# MCU_144_POWER_Clone.net
KiCad netlist of a schematic drawn in Altium Designer
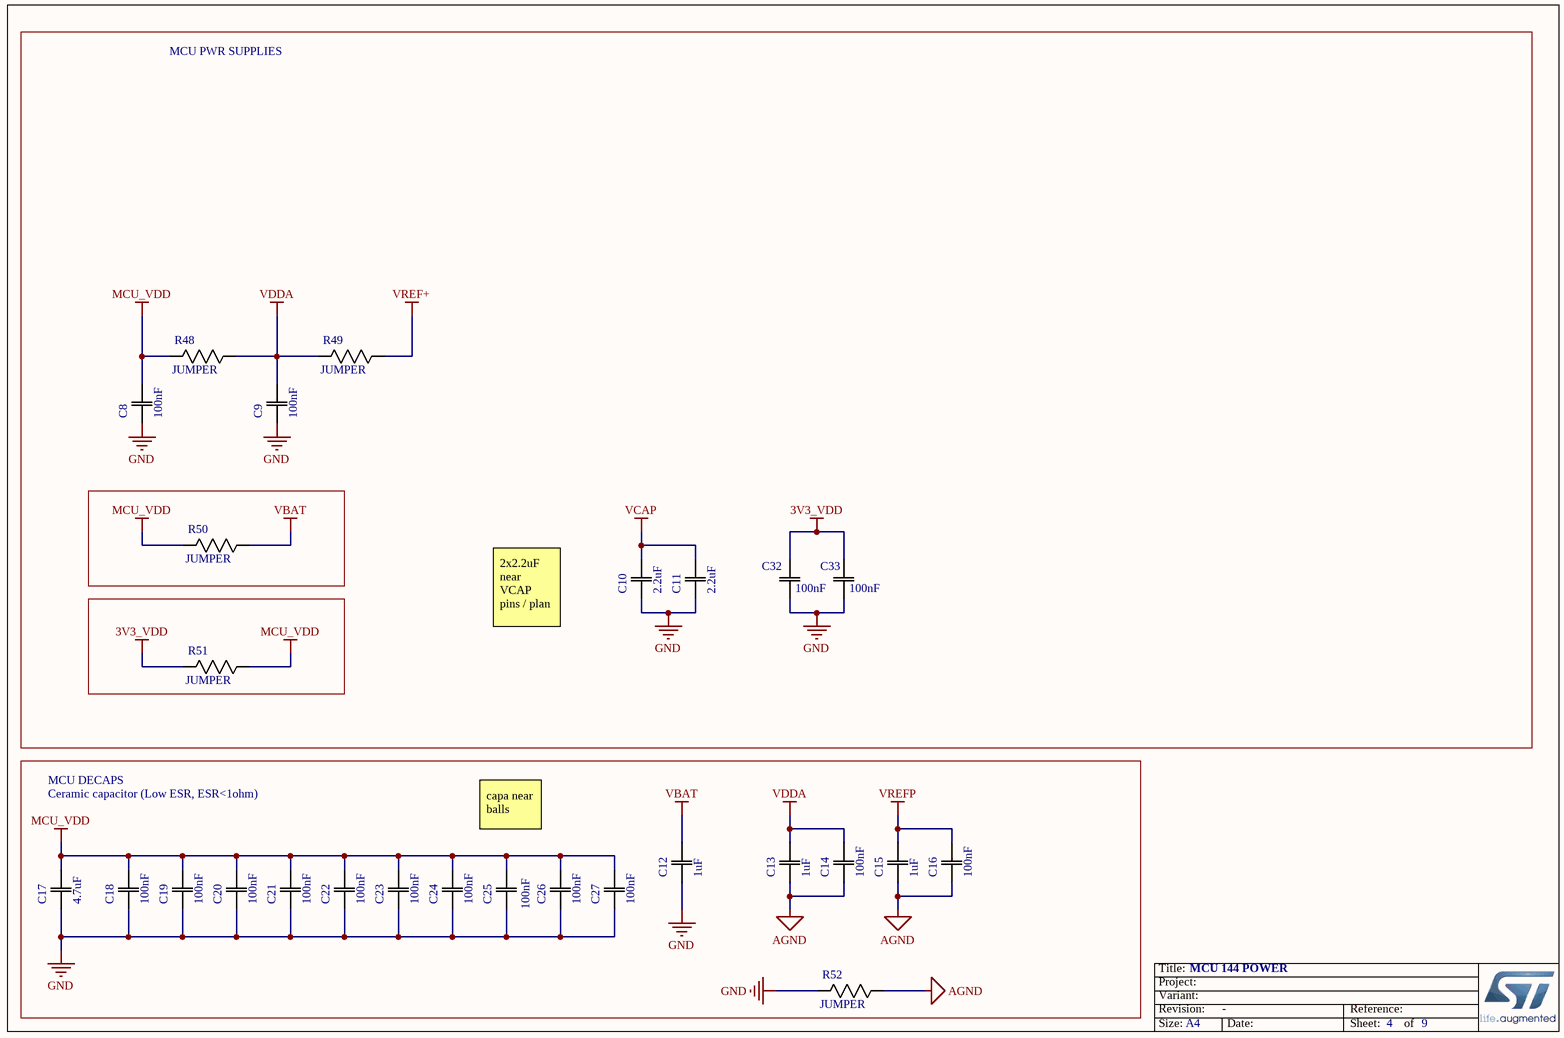
[diagram p0: MCU_144_POWER_Clone.SchDoc]

(export (version "E")
  (design (tool "Eeschema 10.0.6"))
  (components
    (comp (ref "C8")
      (value "100nF")
      (footprint "0805")
      (description "CAP CER 0.1UF 50V X7R 0805")
      (fields (field (name "MP") "CC0805KRX7R9BB104") (field (name "MF") "Yageo"))
      (libsource (lib "AltiumLibraries") (part "CAP 100nF 0805"))
    )
    (comp (ref "C9")
      (value "100nF")
      (footprint "0805")
      (description "CAP CER 0.1UF 50V X7R 0805")
      (fields (field (name "MP") "CC0805KRX7R9BB104") (field (name "MF") "Yageo"))
      (libsource (lib "AltiumLibraries") (part "CAP 100nF 0805"))
    )
    (comp (ref "C10")
      (value "2.2uF")
      (footprint "0805")
      (description "CAP CER 1UF 50V X7R 0805")
      (fields (field (name "MP") "C0805C225K4RACTU") (field (name "MF") "KEMET"))
      (libsource (lib "AltiumLibraries") (part "CAP 2.2uF 0805"))
    )
    (comp (ref "C11")
      (value "2.2uF")
      (footprint "0805")
      (description "CAP CER 1UF 50V X7R 0805")
      (fields (field (name "MP") "C0805C225K4RACTU") (field (name "MF") "KEMET"))
      (libsource (lib "AltiumLibraries") (part "CAP 2.2uF 0805"))
    )
    (comp (ref "C12")
      (value "1uF")
      (footprint "0805")
      (description "CAP CER 1UF 50V X7R 0805")
      (fields (field (name "MP") "CL21B105KBFNNNE") (field (name "MF") "Samsung Electro-Mechanics"))
      (libsource (lib "AltiumLibraries") (part "CAP 1uF 0805"))
    )
    (comp (ref "C13")
      (value "1uF")
      (footprint "0805")
      (description "CAP CER 1UF 50V X7R 0805")
      (fields (field (name "MP") "CL21B105KBFNNNE") (field (name "MF") "Samsung Electro-Mechanics"))
      (libsource (lib "AltiumLibraries") (part "CAP 1uF 0805"))
    )
    (comp (ref "C14")
      (value "100nF")
      (footprint "0805")
      (description "CAP CER 0.1UF 50V X7R 0805")
      (fields (field (name "MP") "CC0805KRX7R9BB104") (field (name "MF") "Yageo"))
      (libsource (lib "AltiumLibraries") (part "CAP 100nF 0805"))
    )
    (comp (ref "C15")
      (value "1uF")
      (footprint "0805")
      (description "CAP CER 1UF 50V X7R 0805")
      (fields (field (name "MP") "CL21B105KBFNNNE") (field (name "MF") "Samsung Electro-Mechanics"))
      (libsource (lib "AltiumLibraries") (part "CAP 1uF 0805"))
    )
    (comp (ref "C16")
      (value "100nF")
      (footprint "0805")
      (description "CAP CER 0.1UF 50V X7R 0805")
      (fields (field (name "MP") "CC0805KRX7R9BB104") (field (name "MF") "Yageo"))
      (libsource (lib "AltiumLibraries") (part "CAP 100nF 0805"))
    )
    (comp (ref "C17")
      (value "4.7uF")
      (footprint "0805")
      (description "CAP CER 4.7UF 25V X5R 0805")
      (fields (field (name "MP") "CL21B475KOFNNNE") (field (name "MF") "Samsung Electro-Mechanics"))
      (libsource (lib "AltiumLibraries") (part "CAP 4.7uF 0805"))
    )
    (comp (ref "C18")
      (value "100nF")
      (footprint "0805")
      (description "CAP CER 0.1UF 50V X7R 0805")
      (fields (field (name "MP") "CC0805KRX7R9BB104") (field (name "MF") "Yageo"))
      (libsource (lib "AltiumLibraries") (part "CAP 100nF 0805"))
    )
    (comp (ref "C19")
      (value "100nF")
      (footprint "0805")
      (description "CAP CER 0.1UF 50V X7R 0805")
      (fields (field (name "MP") "CC0805KRX7R9BB104") (field (name "MF") "Yageo"))
      (libsource (lib "AltiumLibraries") (part "CAP 100nF 0805"))
    )
    (comp (ref "C20")
      (value "100nF")
      (footprint "0805")
      (description "CAP CER 0.1UF 50V X7R 0805")
      (fields (field (name "MP") "CC0805KRX7R9BB104") (field (name "MF") "Yageo"))
      (libsource (lib "AltiumLibraries") (part "CAP 100nF 0805"))
    )
    (comp (ref "C21")
      (value "100nF")
      (footprint "0805")
      (description "CAP CER 0.1UF 50V X7R 0805")
      (fields (field (name "MP") "CC0805KRX7R9BB104") (field (name "MF") "Yageo"))
      (libsource (lib "AltiumLibraries") (part "CAP 100nF 0805"))
    )
    (comp (ref "C22")
      (value "100nF")
      (footprint "0805")
      (description "CAP CER 0.1UF 50V X7R 0805")
      (fields (field (name "MP") "CC0805KRX7R9BB104") (field (name "MF") "Yageo"))
      (libsource (lib "AltiumLibraries") (part "CAP 100nF 0805"))
    )
    (comp (ref "C23")
      (value "100nF")
      (footprint "0805")
      (description "CAP CER 0.1UF 50V X7R 0805")
      (fields (field (name "MP") "CC0805KRX7R9BB104") (field (name "MF") "Yageo"))
      (libsource (lib "AltiumLibraries") (part "CAP 100nF 0805"))
    )
    (comp (ref "C24")
      (value "100nF")
      (footprint "0805")
      (description "CAP CER 0.1UF 50V X7R 0805")
      (fields (field (name "MP") "CC0805KRX7R9BB104") (field (name "MF") "Yageo"))
      (libsource (lib "AltiumLibraries") (part "CAP 100nF 0805"))
    )
    (comp (ref "C25")
      (value "100nF")
      (footprint "0805")
      (description "CAP CER 0.1UF 50V X7R 0805")
      (fields (field (name "MP") "CC0805KRX7R9BB104") (field (name "MF") "Yageo"))
      (libsource (lib "AltiumLibraries") (part "CAP 100nF 0805"))
    )
    (comp (ref "C26")
      (value "100nF")
      (footprint "0805")
      (description "CAP CER 0.1UF 50V X7R 0805")
      (fields (field (name "MP") "CC0805KRX7R9BB104") (field (name "MF") "Yageo"))
      (libsource (lib "AltiumLibraries") (part "CAP 100nF 0805"))
    )
    (comp (ref "C27")
      (value "100nF")
      (footprint "0805")
      (description "CAP CER 0.1UF 50V X7R 0805")
      (fields (field (name "MP") "CC0805KRX7R9BB104") (field (name "MF") "Yageo"))
      (libsource (lib "AltiumLibraries") (part "CAP 100nF 0805"))
    )
    (comp (ref "C32")
      (value "100nF")
      (footprint "0805")
      (description "CAP CER 0.1UF 50V X7R 0805")
      (fields (field (name "MP") "CC0805KRX7R9BB104") (field (name "MF") "Yageo"))
      (libsource (lib "AltiumLibraries") (part "CAP 100nF 0805"))
    )
    (comp (ref "C33")
      (value "100nF")
      (footprint "0805")
      (description "CAP CER 0.1UF 50V X7R 0805")
      (fields (field (name "MP") "CC0805KRX7R9BB104") (field (name "MF") "Yageo"))
      (libsource (lib "AltiumLibraries") (part "CAP 100nF 0805"))
    )
    (comp (ref "R48")
      (value "JUMPER")
      (footprint "0805")
      (description "RES SMD 0 OHM JUMPER 1/8W 0805")
      (fields (field (name "MP") "RC0805JR-070RL") (field (name "MF") "Yageo"))
      (libsource (lib "AltiumLibraries") (part "RES 0 0805"))
    )
    (comp (ref "R49")
      (value "JUMPER")
      (footprint "0805")
      (description "RES SMD 0 OHM JUMPER 1/8W 0805")
      (fields (field (name "MP") "RC0805JR-070RL") (field (name "MF") "Yageo"))
      (libsource (lib "AltiumLibraries") (part "RES 0 0805"))
    )
    (comp (ref "R50")
      (value "JUMPER")
      (footprint "0805")
      (description "RES SMD 0 OHM JUMPER 1/8W 0805")
      (fields (field (name "MP") "RC0805JR-070RL") (field (name "MF") "Yageo"))
      (libsource (lib "AltiumLibraries") (part "RES 0 0805"))
    )
    (comp (ref "R51")
      (value "JUMPER")
      (footprint "0805")
      (description "RES SMD 0 OHM JUMPER 1/8W 0805")
      (fields (field (name "MP") "RC0805JR-070RL") (field (name "MF") "Yageo"))
      (libsource (lib "AltiumLibraries") (part "RES 0 0805"))
    )
    (comp (ref "R52")
      (value "JUMPER")
      (footprint "0805")
      (description "RES SMD 0 OHM JUMPER 1/8W 0805")
      (fields (field (name "MP") "RC0805JR-070RL") (field (name "MF") "Yageo"))
      (libsource (lib "") (part "RES 0 0805_1"))
    )
  )
  (nets
    (net (code "1") (name "3V3_VDD") (class "Default")
      (node (ref "C32") (pin "2") (pinfunction "C2_2") (pintype "passive"))
      (node (ref "C33") (pin "2") (pinfunction "C2_2") (pintype "passive"))
      (node (ref "R51") (pin "2") (pinfunction "R2_2") (pintype "passive"))
    )
    (net (code "2") (name "AGND") (class "Default")
      (node (ref "C13") (pin "1") (pinfunction "C1_1") (pintype "passive"))
      (node (ref "C14") (pin "1") (pinfunction "C1_1") (pintype "passive"))
      (node (ref "C15") (pin "1") (pinfunction "C1_1") (pintype "passive"))
      (node (ref "C16") (pin "1") (pinfunction "C1_1") (pintype "passive"))
      (node (ref "R52") (pin "1") (pinfunction "R1_1") (pintype "passive"))
    )
    (net (code "3") (name "GND") (class "Default")
      (node (ref "C10") (pin "1") (pinfunction "C1_1") (pintype "passive"))
      (node (ref "C11") (pin "1") (pinfunction "C1_1") (pintype "passive"))
      (node (ref "C12") (pin "1") (pinfunction "C1_1") (pintype "passive"))
      (node (ref "C17") (pin "1") (pinfunction "C1_1") (pintype "passive"))
      (node (ref "C18") (pin "1") (pinfunction "C1_1") (pintype "passive"))
      (node (ref "C19") (pin "1") (pinfunction "C1_1") (pintype "passive"))
      (node (ref "C20") (pin "1") (pinfunction "C1_1") (pintype "passive"))
      (node (ref "C21") (pin "1") (pinfunction "C1_1") (pintype "passive"))
      (node (ref "C22") (pin "1") (pinfunction "C1_1") (pintype "passive"))
      (node (ref "C23") (pin "1") (pinfunction "C1_1") (pintype "passive"))
      (node (ref "C24") (pin "1") (pinfunction "C1_1") (pintype "passive"))
      (node (ref "C25") (pin "1") (pinfunction "C1_1") (pintype "passive"))
      (node (ref "C26") (pin "1") (pinfunction "C1_1") (pintype "passive"))
      (node (ref "C27") (pin "1") (pinfunction "C1_1") (pintype "passive"))
      (node (ref "C32") (pin "1") (pinfunction "C1_1") (pintype "passive"))
      (node (ref "C33") (pin "1") (pinfunction "C1_1") (pintype "passive"))
      (node (ref "C8") (pin "1") (pinfunction "C1_1") (pintype "passive"))
      (node (ref "C9") (pin "1") (pinfunction "C1_1") (pintype "passive"))
      (node (ref "R52") (pin "2") (pinfunction "R2_2") (pintype "passive"))
    )
    (net (code "4") (name "MCU_VDD") (class "Default")
      (node (ref "C17") (pin "2") (pinfunction "C2_2") (pintype "passive"))
      (node (ref "C18") (pin "2") (pinfunction "C2_2") (pintype "passive"))
      (node (ref "C19") (pin "2") (pinfunction "C2_2") (pintype "passive"))
      (node (ref "C20") (pin "2") (pinfunction "C2_2") (pintype "passive"))
      (node (ref "C21") (pin "2") (pinfunction "C2_2") (pintype "passive"))
      (node (ref "C22") (pin "2") (pinfunction "C2_2") (pintype "passive"))
      (node (ref "C23") (pin "2") (pinfunction "C2_2") (pintype "passive"))
      (node (ref "C24") (pin "2") (pinfunction "C2_2") (pintype "passive"))
      (node (ref "C25") (pin "2") (pinfunction "C2_2") (pintype "passive"))
      (node (ref "C26") (pin "2") (pinfunction "C2_2") (pintype "passive"))
      (node (ref "C27") (pin "2") (pinfunction "C2_2") (pintype "passive"))
      (node (ref "C8") (pin "2") (pinfunction "C2_2") (pintype "passive"))
      (node (ref "R48") (pin "2") (pinfunction "R2_2") (pintype "passive"))
      (node (ref "R50") (pin "2") (pinfunction "R2_2") (pintype "passive"))
      (node (ref "R51") (pin "1") (pinfunction "R1_1") (pintype "passive"))
    )
    (net (code "5") (name "VBAT") (class "Default")
      (node (ref "C12") (pin "2") (pinfunction "C2_2") (pintype "passive"))
      (node (ref "R50") (pin "1") (pinfunction "R1_1") (pintype "passive"))
    )
    (net (code "6") (name "VCAP") (class "Default")
      (node (ref "C10") (pin "2") (pinfunction "C2_2") (pintype "passive"))
      (node (ref "C11") (pin "2") (pinfunction "C2_2") (pintype "passive"))
    )
    (net (code "7") (name "VDDA") (class "Default")
      (node (ref "C13") (pin "2") (pinfunction "C2_2") (pintype "passive"))
      (node (ref "C14") (pin "2") (pinfunction "C2_2") (pintype "passive"))
      (node (ref "C9") (pin "2") (pinfunction "C2_2") (pintype "passive"))
      (node (ref "R48") (pin "1") (pinfunction "R1_1") (pintype "passive"))
      (node (ref "R49") (pin "2") (pinfunction "R2_2") (pintype "passive"))
    )
    (net (code "8") (name "VREF+") (class "Default")
      (node (ref "R49") (pin "1") (pinfunction "R1_1") (pintype "passive"))
    )
    (net (code "9") (name "VREFP") (class "Default")
      (node (ref "C15") (pin "2") (pinfunction "C2_2") (pintype "passive"))
      (node (ref "C16") (pin "2") (pinfunction "C2_2") (pintype "passive"))
    )
  )
)
